# BusinessCardPCB.net
KiCad netlist of a schematic drawn in EAGLE
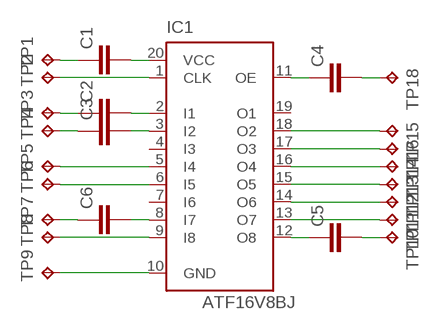
[diagram p0: schematic, sheet 1]

(export (version "E")
  (design (tool "Eeschema 10.0.6"))
  (components
    (comp (ref "C1")
      (value "C-EUC0603K")
      (footprint "eagle-import:C0603K")
      (libsource (lib "eagle-import") (part "C-EUC0603K"))
    )
    (comp (ref "C2")
      (value "C-EUC0603K")
      (footprint "eagle-import:C0603K")
      (libsource (lib "eagle-import") (part "C-EUC0603K"))
    )
    (comp (ref "C3")
      (value "C-EUC0603K")
      (footprint "eagle-import:C0603K")
      (libsource (lib "eagle-import") (part "C-EUC0603K"))
    )
    (comp (ref "C4")
      (value "C-EUC0603K")
      (footprint "eagle-import:C0603K")
      (libsource (lib "eagle-import") (part "C-EUC0603K"))
    )
    (comp (ref "C5")
      (value "C-EUC0603K")
      (footprint "eagle-import:C0603K")
      (libsource (lib "eagle-import") (part "C-EUC0603K"))
    )
    (comp (ref "C6")
      (value "C-EUC0603K")
      (footprint "eagle-import:C0603K")
      (libsource (lib "eagle-import") (part "C-EUC0603K"))
    )
    (comp (ref "IC1")
      (value "ATF16V8BJ")
      (footprint "eagle-import:PLCC20")
      (fields (field (name "MPN") "ATF16V8CZ-15JU"))
      (libsource (lib "eagle-import") (part "ATF16V8BJ"))
    )
    (comp (ref "TP1")
      (value "TPTP10R")
      (footprint "eagle-import:TP10R")
      (libsource (lib "eagle-import") (part "TPTP10R"))
    )
    (comp (ref "TP2")
      (value "TPTP10R")
      (footprint "eagle-import:TP10R")
      (libsource (lib "eagle-import") (part "TPTP10R"))
    )
    (comp (ref "TP3")
      (value "TPTP10R")
      (footprint "eagle-import:TP10R")
      (libsource (lib "eagle-import") (part "TPTP10R"))
    )
    (comp (ref "TP4")
      (value "TPTP10R")
      (footprint "eagle-import:TP10R")
      (libsource (lib "eagle-import") (part "TPTP10R"))
    )
    (comp (ref "TP5")
      (value "TPTP10R")
      (footprint "eagle-import:TP10R")
      (libsource (lib "eagle-import") (part "TPTP10R"))
    )
    (comp (ref "TP6")
      (value "TPTP10R")
      (footprint "eagle-import:TP10R")
      (libsource (lib "eagle-import") (part "TPTP10R"))
    )
    (comp (ref "TP7")
      (value "TPTP10R")
      (footprint "eagle-import:TP10R")
      (libsource (lib "eagle-import") (part "TPTP10R"))
    )
    (comp (ref "TP8")
      (value "TPTP10R")
      (footprint "eagle-import:TP10R")
      (libsource (lib "eagle-import") (part "TPTP10R"))
    )
    (comp (ref "TP9")
      (value "TPTP10R")
      (footprint "eagle-import:TP10R")
      (libsource (lib "eagle-import") (part "TPTP10R"))
    )
    (comp (ref "TP10")
      (value "TPTP10R")
      (footprint "eagle-import:TP10R")
      (libsource (lib "eagle-import") (part "TPTP10R"))
    )
    (comp (ref "TP11")
      (value "TPTP10R")
      (footprint "eagle-import:TP10R")
      (libsource (lib "eagle-import") (part "TPTP10R"))
    )
    (comp (ref "TP12")
      (value "TPTP10R")
      (footprint "eagle-import:TP10R")
      (libsource (lib "eagle-import") (part "TPTP10R"))
    )
    (comp (ref "TP13")
      (value "TPTP10R")
      (footprint "eagle-import:TP10R")
      (libsource (lib "eagle-import") (part "TPTP10R"))
    )
    (comp (ref "TP14")
      (value "TPTP10R")
      (footprint "eagle-import:TP10R")
      (libsource (lib "eagle-import") (part "TPTP10R"))
    )
    (comp (ref "TP15")
      (value "TPTP10R")
      (footprint "eagle-import:TP10R")
      (libsource (lib "eagle-import") (part "TPTP10R"))
    )
    (comp (ref "TP16")
      (value "TPTP10R")
      (footprint "eagle-import:TP10R")
      (libsource (lib "eagle-import") (part "TPTP10R"))
    )
    (comp (ref "TP18")
      (value "TPTP10R")
      (footprint "eagle-import:TP10R")
      (libsource (lib "eagle-import") (part "TPTP10R"))
    )
  )
  (nets
    (net (code "1") (name "Net-(C1-Pad1)") (class "Default")
      (node (ref "C1") (pin "1") (pinfunction "1_1") (pintype "passive"))
      (node (ref "TP1") (pin "TP") (pinfunction "TP_TP") (pintype "input"))
    )
    (net (code "2") (name "Net-(C2-Pad1)") (class "Default")
      (node (ref "C2") (pin "1") (pinfunction "1_1") (pintype "passive"))
      (node (ref "TP3") (pin "TP") (pinfunction "TP_TP") (pintype "input"))
    )
    (net (code "3") (name "Net-(C3-Pad1)") (class "Default")
      (node (ref "C3") (pin "1") (pinfunction "1_1") (pintype "passive"))
      (node (ref "TP4") (pin "TP") (pinfunction "TP_TP") (pintype "input"))
    )
    (net (code "4") (name "Net-(C4-Pad2)") (class "Default")
      (node (ref "C4") (pin "2") (pinfunction "2_2") (pintype "passive"))
      (node (ref "TP18") (pin "TP") (pinfunction "TP_TP") (pintype "input"))
    )
    (net (code "5") (name "Net-(C5-Pad2)") (class "Default")
      (node (ref "C5") (pin "2") (pinfunction "2_2") (pintype "passive"))
      (node (ref "TP10") (pin "TP") (pinfunction "TP_TP") (pintype "input"))
    )
    (net (code "6") (name "Net-(C6-Pad1)") (class "Default")
      (node (ref "C6") (pin "1") (pinfunction "1_1") (pintype "passive"))
      (node (ref "TP7") (pin "TP") (pinfunction "TP_TP") (pintype "input"))
    )
    (net (code "7") (name "Net-(IC1-CLK)") (class "Default")
      (node (ref "IC1") (pin "1") (pinfunction "CLK_1") (pintype "input"))
      (node (ref "TP2") (pin "TP") (pinfunction "TP_TP") (pintype "input"))
    )
    (net (code "8") (name "Net-(IC1-GND)") (class "Default")
      (node (ref "IC1") (pin "10") (pinfunction "GND_10") (pintype "power_in"))
      (node (ref "TP9") (pin "TP") (pinfunction "TP_TP") (pintype "input"))
    )
    (net (code "9") (name "Net-(IC1-I1)") (class "Default")
      (node (ref "C2") (pin "2") (pinfunction "2_2") (pintype "passive"))
      (node (ref "IC1") (pin "2") (pinfunction "I1_2") (pintype "input"))
    )
    (net (code "10") (name "Net-(IC1-I2)") (class "Default")
      (node (ref "C3") (pin "2") (pinfunction "2_2") (pintype "passive"))
      (node (ref "IC1") (pin "3") (pinfunction "I2_3") (pintype "input"))
    )
    (net (code "11") (name "Net-(IC1-I4)") (class "Default")
      (node (ref "IC1") (pin "5") (pinfunction "I4_5") (pintype "input"))
      (node (ref "TP5") (pin "TP") (pinfunction "TP_TP") (pintype "input"))
    )
    (net (code "12") (name "Net-(IC1-I5)") (class "Default")
      (node (ref "IC1") (pin "6") (pinfunction "I5_6") (pintype "input"))
      (node (ref "TP6") (pin "TP") (pinfunction "TP_TP") (pintype "input"))
    )
    (net (code "13") (name "Net-(IC1-I7)") (class "Default")
      (node (ref "C6") (pin "2") (pinfunction "2_2") (pintype "passive"))
      (node (ref "IC1") (pin "8") (pinfunction "I7_8") (pintype "input"))
    )
    (net (code "14") (name "Net-(IC1-I8)") (class "Default")
      (node (ref "IC1") (pin "9") (pinfunction "I8_9") (pintype "input"))
      (node (ref "TP8") (pin "TP") (pinfunction "TP_TP") (pintype "input"))
    )
    (net (code "15") (name "Net-(IC1-O2)") (class "Default")
      (node (ref "IC1") (pin "18") (pinfunction "O2_18") (pintype "output"))
      (node (ref "TP15") (pin "TP") (pinfunction "TP_TP") (pintype "input"))
    )
    (net (code "16") (name "Net-(IC1-O3)") (class "Default")
      (node (ref "IC1") (pin "17") (pinfunction "O3_17") (pintype "output"))
      (node (ref "TP16") (pin "TP") (pinfunction "TP_TP") (pintype "input"))
    )
    (net (code "17") (name "Net-(IC1-O4)") (class "Default")
      (node (ref "IC1") (pin "16") (pinfunction "O4_16") (pintype "output"))
      (node (ref "TP14") (pin "TP") (pinfunction "TP_TP") (pintype "input"))
    )
    (net (code "18") (name "Net-(IC1-O5)") (class "Default")
      (node (ref "IC1") (pin "15") (pinfunction "O5_15") (pintype "output"))
      (node (ref "TP13") (pin "TP") (pinfunction "TP_TP") (pintype "input"))
    )
    (net (code "19") (name "Net-(IC1-O6)") (class "Default")
      (node (ref "IC1") (pin "14") (pinfunction "O6_14") (pintype "output"))
      (node (ref "TP12") (pin "TP") (pinfunction "TP_TP") (pintype "input"))
    )
    (net (code "20") (name "Net-(IC1-O7)") (class "Default")
      (node (ref "IC1") (pin "13") (pinfunction "O7_13") (pintype "output"))
      (node (ref "TP11") (pin "TP") (pinfunction "TP_TP") (pintype "input"))
    )
    (net (code "21") (name "Net-(IC1-O8)") (class "Default")
      (node (ref "C5") (pin "1") (pinfunction "1_1") (pintype "passive"))
      (node (ref "IC1") (pin "12") (pinfunction "O8_12") (pintype "output"))
    )
    (net (code "22") (name "Net-(IC1-OE)") (class "Default")
      (node (ref "C4") (pin "1") (pinfunction "1_1") (pintype "passive"))
      (node (ref "IC1") (pin "11") (pinfunction "OE_11") (pintype "input"))
    )
    (net (code "23") (name "Net-(IC1-VCC)") (class "Default")
      (node (ref "C1") (pin "2") (pinfunction "2_2") (pintype "passive"))
      (node (ref "IC1") (pin "20") (pinfunction "VCC_20") (pintype "power_in"))
    )
    (net (code "24") (name "unconnected-(IC1-I3-Pad4)") (class "Default")
      (node (ref "IC1") (pin "4") (pinfunction "I3_4") (pintype "input"))
    )
    (net (code "25") (name "unconnected-(IC1-I6-Pad7)") (class "Default")
      (node (ref "IC1") (pin "7") (pinfunction "I6_7") (pintype "input"))
    )
    (net (code "26") (name "unconnected-(IC1-O1-Pad19)") (class "Default")
      (node (ref "IC1") (pin "19") (pinfunction "O1_19") (pintype "output"))
    )
  )
)
